# amplis.net
KiCad netlist of a schematic drawn in Altium Designer
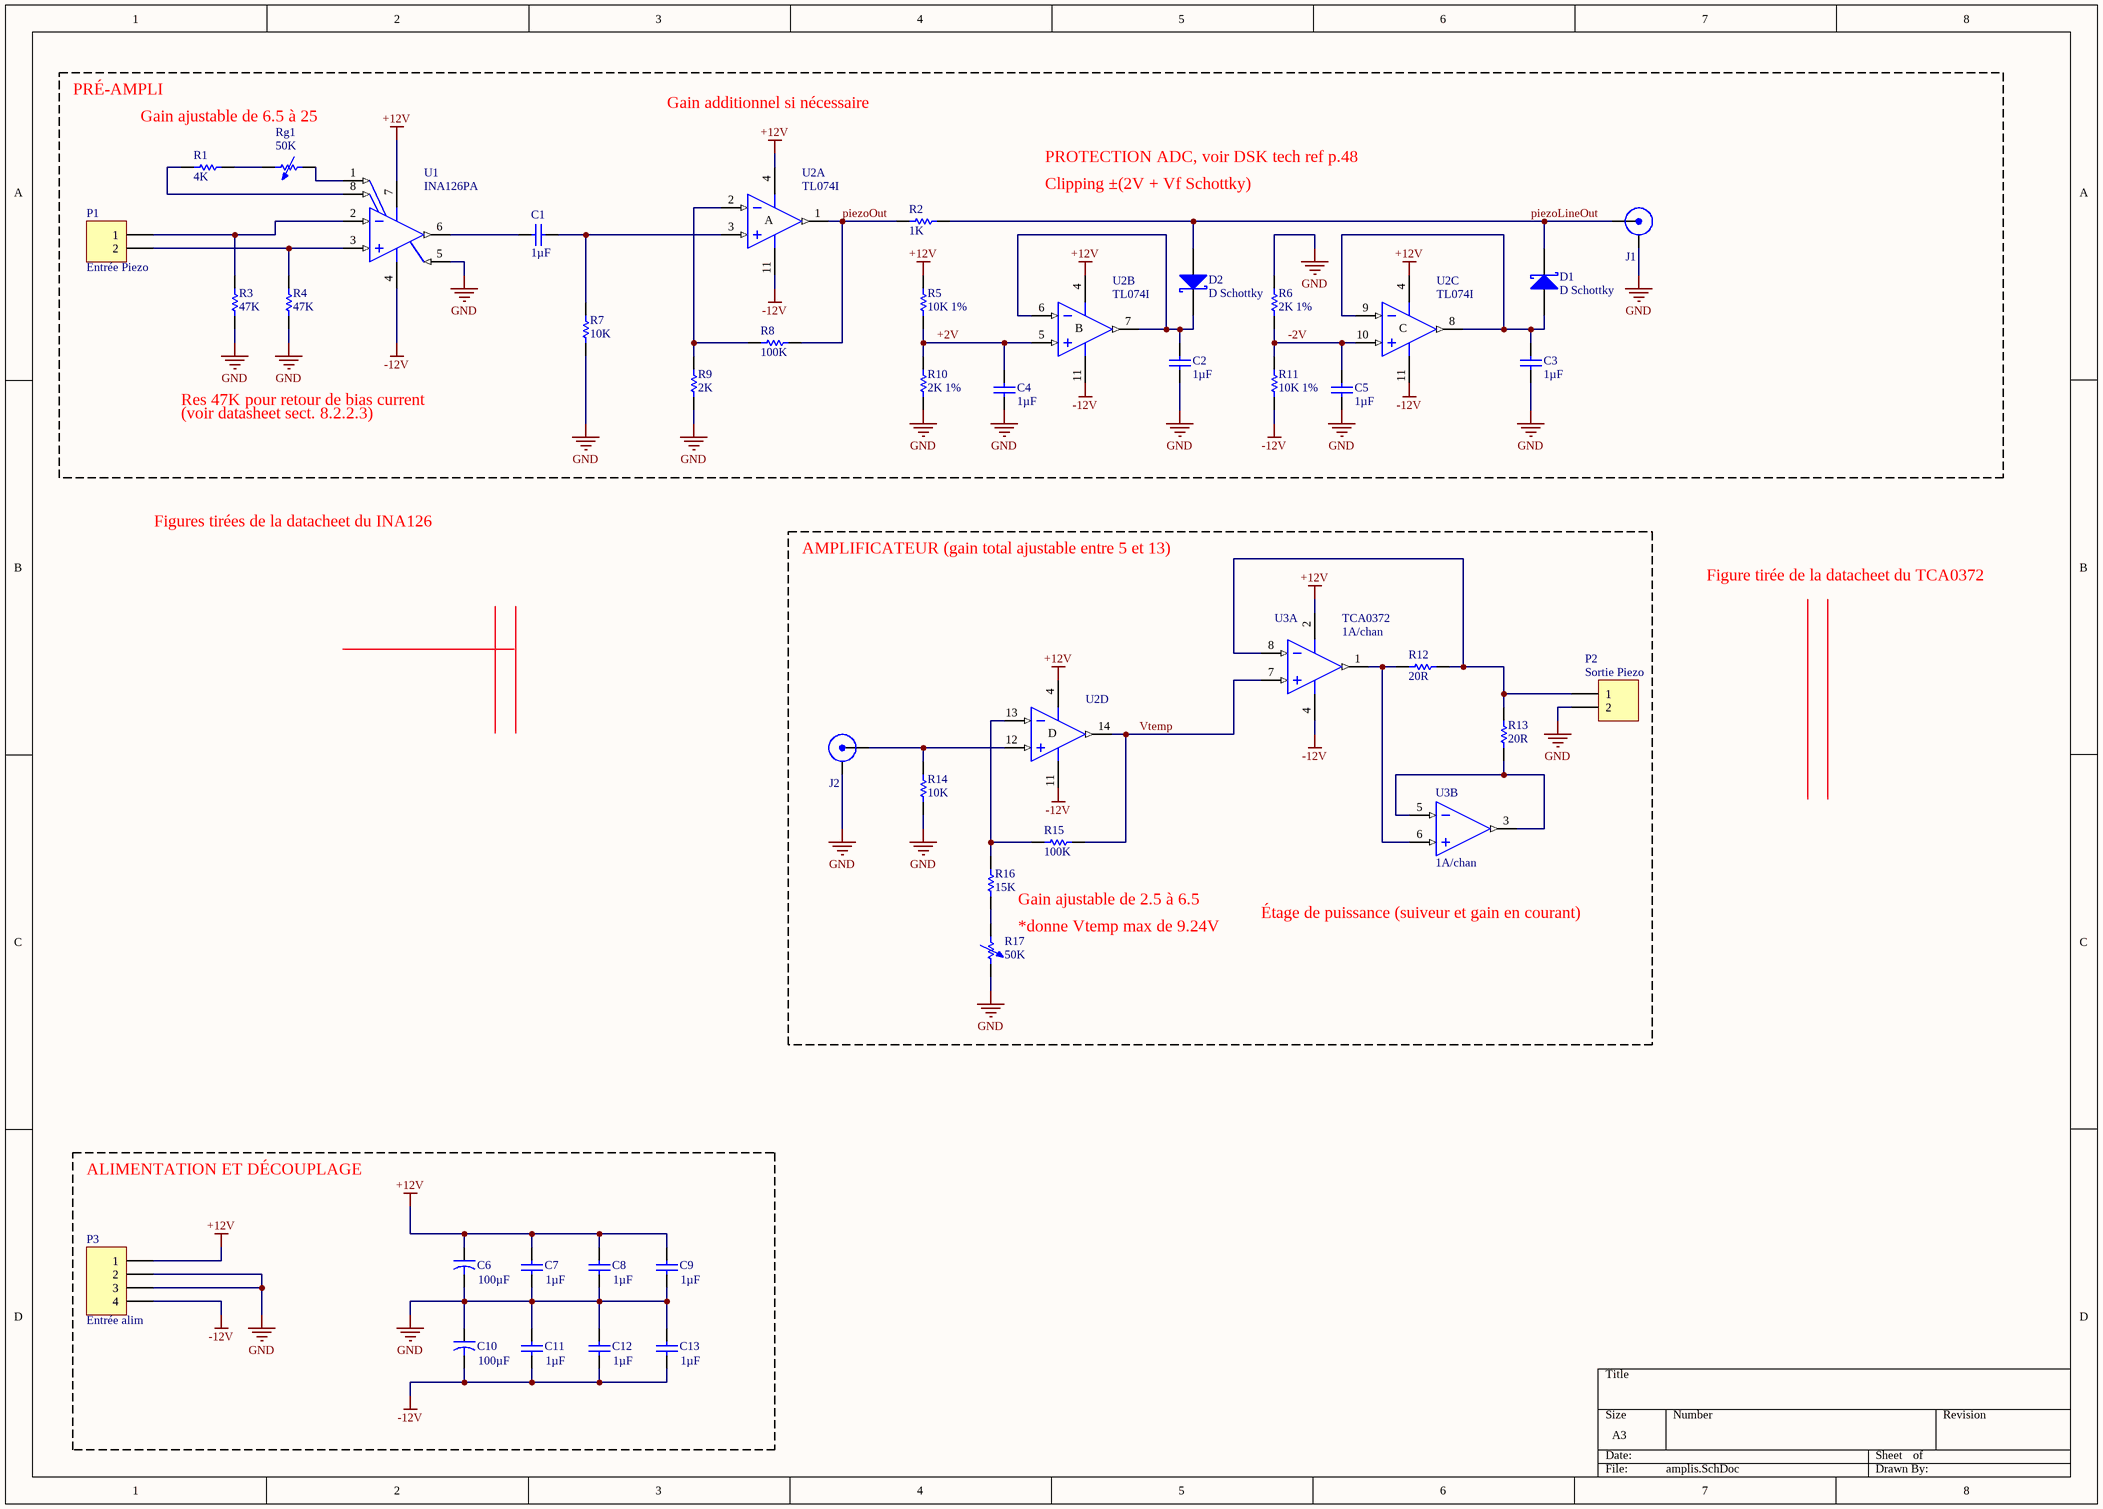
[diagram p0: amplis.SchDoc]

(export (version "E")
  (design (tool "Eeschema 10.0.6"))
  (components
    (comp (ref "C1")
      (value "1µF")
      (footprint "RAD-0.3")
      (description "Capacitor")
      (fields (field (name "Comment") "Cap") (field (name "PUBLISHER") "Altium Limited"))
      (libsource (lib "Miscellaneous Devices") (part "Cap"))
    )
    (comp (ref "C2")
      (value "1µF")
      (footprint "RAD-0.3")
      (description "Capacitor")
      (fields (field (name "Comment") "Cap") (field (name "PUBLISHER") "Altium Limited"))
      (libsource (lib "Miscellaneous Devices") (part "Cap"))
    )
    (comp (ref "C3")
      (value "1µF")
      (footprint "RAD-0.3")
      (description "Capacitor")
      (fields (field (name "Comment") "Cap") (field (name "PUBLISHER") "Altium Limited"))
      (libsource (lib "Miscellaneous Devices") (part "Cap"))
    )
    (comp (ref "C4")
      (value "1µF")
      (footprint "RAD-0.3")
      (description "Capacitor")
      (fields (field (name "Comment") "Cap") (field (name "PUBLISHER") "Altium Limited"))
      (libsource (lib "Miscellaneous Devices") (part "Cap"))
    )
    (comp (ref "C5")
      (value "1µF")
      (footprint "RAD-0.3")
      (description "Capacitor")
      (fields (field (name "Comment") "Cap") (field (name "PUBLISHER") "Altium Limited"))
      (libsource (lib "Miscellaneous Devices") (part "Cap"))
    )
    (comp (ref "C6")
      (value "100µF")
      (footprint "CAPR5-4X5")
      (description "Capacitor")
      (fields (field (name "Comment") "Cap2") (field (name "PUBLISHER") "Altium Limited"))
      (libsource (lib "Miscellaneous Devices") (part "Cap2"))
    )
    (comp (ref "C7")
      (value "1µF")
      (footprint "RAD-0.3")
      (description "Capacitor")
      (fields (field (name "Comment") "Cap") (field (name "PUBLISHER") "Altium Limited"))
      (libsource (lib "Miscellaneous Devices") (part "Cap"))
    )
    (comp (ref "C8")
      (value "1µF")
      (footprint "RAD-0.3")
      (description "Capacitor")
      (fields (field (name "Comment") "Cap") (field (name "PUBLISHER") "Altium Limited"))
      (libsource (lib "Miscellaneous Devices") (part "Cap"))
    )
    (comp (ref "C9")
      (value "1µF")
      (footprint "RAD-0.3")
      (description "Capacitor")
      (fields (field (name "Comment") "Cap") (field (name "PUBLISHER") "Altium Limited"))
      (libsource (lib "Miscellaneous Devices") (part "Cap"))
    )
    (comp (ref "C10")
      (value "100µF")
      (footprint "CAPR5-4X5")
      (description "Capacitor")
      (fields (field (name "Comment") "Cap2") (field (name "PUBLISHER") "Altium Limited"))
      (libsource (lib "Miscellaneous Devices") (part "Cap2"))
    )
    (comp (ref "C11")
      (value "1µF")
      (footprint "RAD-0.3")
      (description "Capacitor")
      (fields (field (name "Comment") "Cap") (field (name "PUBLISHER") "Altium Limited"))
      (libsource (lib "Miscellaneous Devices") (part "Cap"))
    )
    (comp (ref "C12")
      (value "1µF")
      (footprint "RAD-0.3")
      (description "Capacitor")
      (fields (field (name "Comment") "Cap") (field (name "PUBLISHER") "Altium Limited"))
      (libsource (lib "Miscellaneous Devices") (part "Cap"))
    )
    (comp (ref "C13")
      (value "1µF")
      (footprint "RAD-0.3")
      (description "Capacitor")
      (fields (field (name "Comment") "Cap") (field (name "PUBLISHER") "Altium Limited"))
      (libsource (lib "Miscellaneous Devices") (part "Cap"))
    )
    (comp (ref "D1")
      (value "D Schottky")
      (footprint "SMB")
      (description "Schottky Diode")
      (fields (field (name "PUBLISHER") "Altium Limited"))
      (libsource (lib "Miscellaneous Devices") (part "D Schottky"))
    )
    (comp (ref "D2")
      (value "D Schottky")
      (footprint "SMB")
      (description "Schottky Diode")
      (fields (field (name "PUBLISHER") "Altium Limited"))
      (libsource (lib "Miscellaneous Devices") (part "D Schottky"))
    )
    (comp (ref "J1") (value "BNC") (footprint "BNC_Vertical") (libsource (lib "S3_projet") (part "BNC")))
    (comp (ref "J2") (value "BNC") (footprint "BNC_Vertical") (libsource (lib "S3_projet") (part "BNC")))
    (comp (ref "P1")
      (value "Entrée Piezo")
      (footprint "HDR1X2")
      (description "Header, 2-Pin")
      (fields (field (name "PUBLISHER") "Altium Limited"))
      (libsource (lib "") (part "Header 2_1"))
    )
    (comp (ref "P2")
      (value "Sortie Piezo")
      (footprint "HDR1X2")
      (description "Header, 2-Pin")
      (fields (field (name "PUBLISHER") "Altium Limited"))
      (libsource (lib "Miscellaneous Connectors") (part "Header 2"))
    )
    (comp (ref "P3")
      (value "Entrée alim")
      (footprint "HDR1X4")
      (description "Header, 4-Pin")
      (fields (field (name "PUBLISHER") "Altium Limited"))
      (libsource (lib "Miscellaneous Connectors") (part "Header 4"))
    )
    (comp (ref "R1")
      (value "4K")
      (footprint "AXIAL-0.3")
      (description "Resistor")
      (fields (field (name "Comment") "Res1") (field (name "PUBLISHER") "Altium Limited"))
      (libsource (lib "Miscellaneous Devices") (part "Res1"))
    )
    (comp (ref "R2")
      (value "1K")
      (footprint "AXIAL-0.3")
      (description "Resistor")
      (fields (field (name "Comment") "Res1") (field (name "PUBLISHER") "Altium Limited"))
      (libsource (lib "Miscellaneous Devices") (part "Res1"))
    )
    (comp (ref "R3")
      (value "47K")
      (footprint "AXIAL-0.3")
      (description "Resistor")
      (fields (field (name "Comment") "Res1") (field (name "PUBLISHER") "Altium Limited"))
      (libsource (lib "Miscellaneous Devices") (part "Res1"))
    )
    (comp (ref "R4")
      (value "47K")
      (footprint "AXIAL-0.3")
      (description "Resistor")
      (fields (field (name "Comment") "Res1") (field (name "PUBLISHER") "Altium Limited"))
      (libsource (lib "Miscellaneous Devices") (part "Res1"))
    )
    (comp (ref "R5")
      (value "10K 1%")
      (footprint "AXIAL-0.3")
      (description "Resistor")
      (fields (field (name "Comment") "Res1") (field (name "PUBLISHER") "Altium Limited"))
      (libsource (lib "Miscellaneous Devices") (part "Res1"))
    )
    (comp (ref "R6")
      (value "2K 1%")
      (footprint "AXIAL-0.3")
      (description "Resistor")
      (fields (field (name "Comment") "Res1") (field (name "PUBLISHER") "Altium Limited"))
      (libsource (lib "Miscellaneous Devices") (part "Res1"))
    )
    (comp (ref "R7")
      (value "10K")
      (footprint "AXIAL-0.3")
      (description "Resistor")
      (fields (field (name "Comment") "Res1") (field (name "PUBLISHER") "Altium Limited"))
      (libsource (lib "Miscellaneous Devices") (part "Res1"))
    )
    (comp (ref "R8")
      (value "100K")
      (footprint "AXIAL-0.3")
      (description "Resistor")
      (fields (field (name "Comment") "Res1") (field (name "PUBLISHER") "Altium Limited"))
      (libsource (lib "Miscellaneous Devices") (part "Res1"))
    )
    (comp (ref "R9")
      (value "2K")
      (footprint "AXIAL-0.3")
      (description "Resistor")
      (fields (field (name "Comment") "Res1") (field (name "PUBLISHER") "Altium Limited"))
      (libsource (lib "Miscellaneous Devices") (part "Res1"))
    )
    (comp (ref "R10")
      (value "2K 1%")
      (footprint "AXIAL-0.3")
      (description "Resistor")
      (fields (field (name "Comment") "Res1") (field (name "PUBLISHER") "Altium Limited"))
      (libsource (lib "Miscellaneous Devices") (part "Res1"))
    )
    (comp (ref "R11")
      (value "10K 1%")
      (footprint "AXIAL-0.3")
      (description "Resistor")
      (fields (field (name "Comment") "Res1") (field (name "PUBLISHER") "Altium Limited"))
      (libsource (lib "Miscellaneous Devices") (part "Res1"))
    )
    (comp (ref "R12")
      (value "20R")
      (footprint "AXIAL-0.3")
      (description "Resistor")
      (fields (field (name "Comment") "Res1") (field (name "PUBLISHER") "Altium Limited"))
      (libsource (lib "Miscellaneous Devices") (part "Res1"))
    )
    (comp (ref "R13")
      (value "20R")
      (footprint "AXIAL-0.3")
      (description "Resistor")
      (fields (field (name "Comment") "Res1") (field (name "PUBLISHER") "Altium Limited"))
      (libsource (lib "Miscellaneous Devices") (part "Res1"))
    )
    (comp (ref "R14")
      (value "10K")
      (footprint "AXIAL-0.3")
      (description "Resistor")
      (fields (field (name "Comment") "Res1") (field (name "PUBLISHER") "Altium Limited"))
      (libsource (lib "Miscellaneous Devices") (part "Res1"))
    )
    (comp (ref "R15")
      (value "100K")
      (footprint "AXIAL-0.3")
      (description "Resistor")
      (fields (field (name "Comment") "Res1") (field (name "PUBLISHER") "Altium Limited"))
      (libsource (lib "Miscellaneous Devices") (part "Res1"))
    )
    (comp (ref "R16")
      (value "15K")
      (footprint "AXIAL-0.3")
      (description "Resistor")
      (fields (field (name "Comment") "Res1") (field (name "PUBLISHER") "Altium Limited"))
      (libsource (lib "Miscellaneous Devices") (part "Res1"))
    )
    (comp (ref "R17")
      (value "50K")
      (footprint "AXIAL-0.7")
      (description "Variable Resistor")
      (fields (field (name "Comment") "Res Adj1") (field (name "PUBLISHER") "Altium Limited"))
      (libsource (lib "Miscellaneous Devices") (part "Res Adj1"))
    )
    (comp (ref "Rg1")
      (value "50K")
      (footprint "AXIAL-0.7")
      (description "Variable Resistor")
      (fields (field (name "Comment") "Res Adj1") (field (name "PUBLISHER") "Altium Limited"))
      (libsource (lib "Miscellaneous Devices") (part "Res Adj1"))
    )
    (comp (ref "U1")
      (value "INA126PA")
      (footprint "TI-P8")
      (fields (field (name "MANUFACTURER") "Texas Instruments"))
      (libsource (lib "TI Amplifiers and Linear Instrumentation Amplifier") (part "INA126PA"))
    )
    (comp (ref "U2")
      (value "TL074I")
      (footprint "SOIC-14")
      (description "Low-Noise J-FET Quad Operational Amplifier")
      (fields (field (name "PUBLISHER") "Altium Limited"))
      (libsource (lib "S3_projet") (part "TL074I"))
    )
    (comp (ref "U3")
      (value "1A/chan")
      (fields (field (name "MODEL") "TCA0372"))
      (libsource (lib "lib_projet") (part "TCA0372_case626"))
    )
  )
  (nets
    (net (code "1") (name "+12V") (class "Default")
      (node (ref "C6") (pin "1") (pinfunction "1_1") (pintype "passive"))
      (node (ref "C7") (pin "2") (pinfunction "2_2") (pintype "passive"))
      (node (ref "C8") (pin "2") (pinfunction "2_2") (pintype "passive"))
      (node (ref "C9") (pin "2") (pinfunction "2_2") (pintype "passive"))
      (node (ref "P3") (pin "1") (pinfunction "1_1") (pintype "passive"))
      (node (ref "R5") (pin "1") (pinfunction "1_1") (pintype "passive"))
      (node (ref "U1") (pin "7") (pinfunction "V+_7") (pintype "power_in"))
      (node (ref "U2") (pin "4") (pinfunction "V+_4") (pintype "power_in"))
      (node (ref "U3") (pin "2") (pinfunction "V+_2") (pintype "power_in"))
    )
    (net (code "2") (name "-12V") (class "Default")
      (node (ref "C10") (pin "2") (pinfunction "2_2") (pintype "passive"))
      (node (ref "C11") (pin "1") (pinfunction "1_1") (pintype "passive"))
      (node (ref "C12") (pin "1") (pinfunction "1_1") (pintype "passive"))
      (node (ref "C13") (pin "1") (pinfunction "1_1") (pintype "passive"))
      (node (ref "P3") (pin "4") (pinfunction "4_4") (pintype "passive"))
      (node (ref "R11") (pin "2") (pinfunction "2_2") (pintype "passive"))
      (node (ref "U1") (pin "4") (pinfunction "V-_4") (pintype "power_in"))
      (node (ref "U2") (pin "11") (pinfunction "V-_11") (pintype "power_in"))
      (node (ref "U3") (pin "4") (pinfunction "V-_4") (pintype "power_in"))
    )
    (net (code "3") (name "/+2V") (class "Default")
      (node (ref "C4") (pin "1") (pinfunction "1_1") (pintype "passive"))
      (node (ref "R10") (pin "1") (pinfunction "1_1") (pintype "passive"))
      (node (ref "R5") (pin "2") (pinfunction "2_2") (pintype "passive"))
      (node (ref "U2") (pin "5") (pinfunction "IN+_5") (pintype "input"))
    )
    (net (code "4") (name "/-2V") (class "Default")
      (node (ref "C5") (pin "1") (pinfunction "1_1") (pintype "passive"))
      (node (ref "R11") (pin "1") (pinfunction "1_1") (pintype "passive"))
      (node (ref "R6") (pin "2") (pinfunction "2_2") (pintype "passive"))
      (node (ref "U2") (pin "10") (pinfunction "IN+_10") (pintype "input"))
    )
    (net (code "5") (name "/Vtemp") (class "Default")
      (node (ref "R15") (pin "1") (pinfunction "1_1") (pintype "passive"))
      (node (ref "U2") (pin "14") (pinfunction "OUT_14") (pintype "output"))
      (node (ref "U3") (pin "7") (pinfunction "VIN+_7") (pintype "input"))
    )
    (net (code "6") (name "/piezoLineOut") (class "Default")
      (node (ref "D1") (pin "2") (pinfunction "K_2") (pintype "passive"))
      (node (ref "D2") (pin "1") (pinfunction "A_1") (pintype "passive"))
      (node (ref "J1") (pin "1") (pinfunction "Sig_1") (pintype "passive"))
      (node (ref "R2") (pin "1") (pinfunction "1_1") (pintype "passive"))
    )
    (net (code "7") (name "/piezoOut") (class "Default")
      (node (ref "R2") (pin "2") (pinfunction "2_2") (pintype "passive"))
      (node (ref "R8") (pin "1") (pinfunction "1_1") (pintype "passive"))
      (node (ref "U2") (pin "1") (pinfunction "OUT_1") (pintype "output"))
    )
    (net (code "8") (name "GND") (class "Default")
      (node (ref "C10") (pin "1") (pinfunction "1_1") (pintype "passive"))
      (node (ref "C11") (pin "2") (pinfunction "2_2") (pintype "passive"))
      (node (ref "C12") (pin "2") (pinfunction "2_2") (pintype "passive"))
      (node (ref "C13") (pin "2") (pinfunction "2_2") (pintype "passive"))
      (node (ref "C2") (pin "2") (pinfunction "2_2") (pintype "passive"))
      (node (ref "C3") (pin "2") (pinfunction "2_2") (pintype "passive"))
      (node (ref "C4") (pin "2") (pinfunction "2_2") (pintype "passive"))
      (node (ref "C5") (pin "2") (pinfunction "2_2") (pintype "passive"))
      (node (ref "C6") (pin "2") (pinfunction "2_2") (pintype "passive"))
      (node (ref "C7") (pin "1") (pinfunction "1_1") (pintype "passive"))
      (node (ref "C8") (pin "1") (pinfunction "1_1") (pintype "passive"))
      (node (ref "C9") (pin "1") (pinfunction "1_1") (pintype "passive"))
      (node (ref "J1") (pin "2") (pinfunction "Gnd_2") (pintype "passive"))
      (node (ref "J2") (pin "2") (pinfunction "Gnd_2") (pintype "passive"))
      (node (ref "P2") (pin "2") (pinfunction "2_2") (pintype "passive"))
      (node (ref "P3") (pin "2") (pinfunction "2_2") (pintype "passive"))
      (node (ref "P3") (pin "3") (pinfunction "3_3") (pintype "passive"))
      (node (ref "R10") (pin "2") (pinfunction "2_2") (pintype "passive"))
      (node (ref "R14") (pin "2") (pinfunction "2_2") (pintype "passive"))
      (node (ref "R17") (pin "2") (pinfunction "2_2") (pintype "passive"))
      (node (ref "R3") (pin "1") (pinfunction "1_1") (pintype "passive"))
      (node (ref "R4") (pin "1") (pinfunction "1_1") (pintype "passive"))
      (node (ref "R6") (pin "1") (pinfunction "1_1") (pintype "passive"))
      (node (ref "R7") (pin "2") (pinfunction "2_2") (pintype "passive"))
      (node (ref "R9") (pin "2") (pinfunction "2_2") (pintype "passive"))
      (node (ref "U1") (pin "5") (pinfunction "REF_5") (pintype "input"))
    )
    (net (code "9") (name "Net-(D1-A)") (class "Default")
      (node (ref "C3") (pin "1") (pinfunction "1_1") (pintype "passive"))
      (node (ref "D1") (pin "1") (pinfunction "A_1") (pintype "passive"))
      (node (ref "U2") (pin "8") (pinfunction "OUT_8") (pintype "output"))
      (node (ref "U2") (pin "9") (pinfunction "IN-_9") (pintype "input"))
    )
    (net (code "10") (name "Net-(D2-K)") (class "Default")
      (node (ref "C2") (pin "1") (pinfunction "1_1") (pintype "passive"))
      (node (ref "D2") (pin "2") (pinfunction "K_2") (pintype "passive"))
      (node (ref "U2") (pin "6") (pinfunction "IN-_6") (pintype "input"))
      (node (ref "U2") (pin "7") (pinfunction "OUT_7") (pintype "output"))
    )
    (net (code "11") (name "Net-(J2-Sig)") (class "Default")
      (node (ref "J2") (pin "1") (pinfunction "Sig_1") (pintype "passive"))
      (node (ref "R14") (pin "1") (pinfunction "1_1") (pintype "passive"))
      (node (ref "U2") (pin "12") (pinfunction "IN+_12") (pintype "input"))
    )
    (net (code "12") (name "Net-(R1-Pad1)") (class "Default")
      (node (ref "R1") (pin "1") (pinfunction "1_1") (pintype "passive"))
      (node (ref "Rg1") (pin "2") (pinfunction "2_2") (pintype "passive"))
    )
    (net (code "13") (name "Net-(R1-Pad2)") (class "Default")
      (node (ref "R1") (pin "2") (pinfunction "2_2") (pintype "passive"))
      (node (ref "U1") (pin "8") (pinfunction "RG_8") (pintype "input"))
    )
    (net (code "14") (name "Net-(R16-Pad2)") (class "Default")
      (node (ref "R16") (pin "2") (pinfunction "2_2") (pintype "passive"))
      (node (ref "R17") (pin "1") (pinfunction "1_1") (pintype "passive"))
    )
    (net (code "15") (name "Net-(Rg1-Pad1)") (class "Default")
      (node (ref "Rg1") (pin "1") (pinfunction "1_1") (pintype "passive"))
      (node (ref "U1") (pin "1") (pinfunction "RG_1") (pintype "input"))
    )
    (net (code "16") (name "Net-(U1-VIN+)") (class "Default")
      (node (ref "P1") (pin "2") (pinfunction "2_2") (pintype "passive"))
      (node (ref "R4") (pin "2") (pinfunction "2_2") (pintype "passive"))
      (node (ref "U1") (pin "3") (pinfunction "VIN+_3") (pintype "input"))
    )
    (net (code "17") (name "Net-(U1-VIN-)") (class "Default")
      (node (ref "P1") (pin "1") (pinfunction "1_1") (pintype "passive"))
      (node (ref "R3") (pin "2") (pinfunction "2_2") (pintype "passive"))
      (node (ref "U1") (pin "2") (pinfunction "VIN-_2") (pintype "input"))
    )
    (net (code "18") (name "Net-(U1-VO)") (class "Default")
      (node (ref "C1") (pin "2") (pinfunction "2_2") (pintype "passive"))
      (node (ref "U1") (pin "6") (pinfunction "VO_6") (pintype "output"))
    )
    (net (code "19") (name "Net-(U2A-IN+)") (class "Default")
      (node (ref "C1") (pin "1") (pinfunction "1_1") (pintype "passive"))
      (node (ref "R7") (pin "1") (pinfunction "1_1") (pintype "passive"))
      (node (ref "U2") (pin "3") (pinfunction "IN+_3") (pintype "input"))
    )
    (net (code "20") (name "Net-(U2A-IN-)") (class "Default")
      (node (ref "R8") (pin "2") (pinfunction "2_2") (pintype "passive"))
      (node (ref "R9") (pin "1") (pinfunction "1_1") (pintype "passive"))
      (node (ref "U2") (pin "2") (pinfunction "IN-_2") (pintype "input"))
    )
    (net (code "21") (name "Net-(U2D-IN-)") (class "Default")
      (node (ref "R15") (pin "2") (pinfunction "2_2") (pintype "passive"))
      (node (ref "R16") (pin "1") (pinfunction "1_1") (pintype "passive"))
      (node (ref "U2") (pin "13") (pinfunction "IN-_13") (pintype "input"))
    )
    (net (code "22") (name "Net-(U3A-VIN-)") (class "Default")
      (node (ref "P2") (pin "1") (pinfunction "1_1") (pintype "passive"))
      (node (ref "R12") (pin "1") (pinfunction "1_1") (pintype "passive"))
      (node (ref "R13") (pin "1") (pinfunction "1_1") (pintype "passive"))
      (node (ref "U3") (pin "8") (pinfunction "VIN-_8") (pintype "input"))
    )
    (net (code "23") (name "Net-(U3A-VOUT)") (class "Default")
      (node (ref "R12") (pin "2") (pinfunction "2_2") (pintype "passive"))
      (node (ref "U3") (pin "1") (pinfunction "VOUT_1") (pintype "output"))
      (node (ref "U3") (pin "6") (pinfunction "VIN+_6") (pintype "input"))
    )
    (net (code "24") (name "Net-(U3B-VIN-)") (class "Default")
      (node (ref "R13") (pin "2") (pinfunction "2_2") (pintype "passive"))
      (node (ref "U3") (pin "3") (pinfunction "VOUT_3") (pintype "output"))
      (node (ref "U3") (pin "5") (pinfunction "VIN-_5") (pintype "input"))
    )
  )
)
